# level_shifter_booster_pack.net
KiCad netlist of a schematic drawn in EAGLE
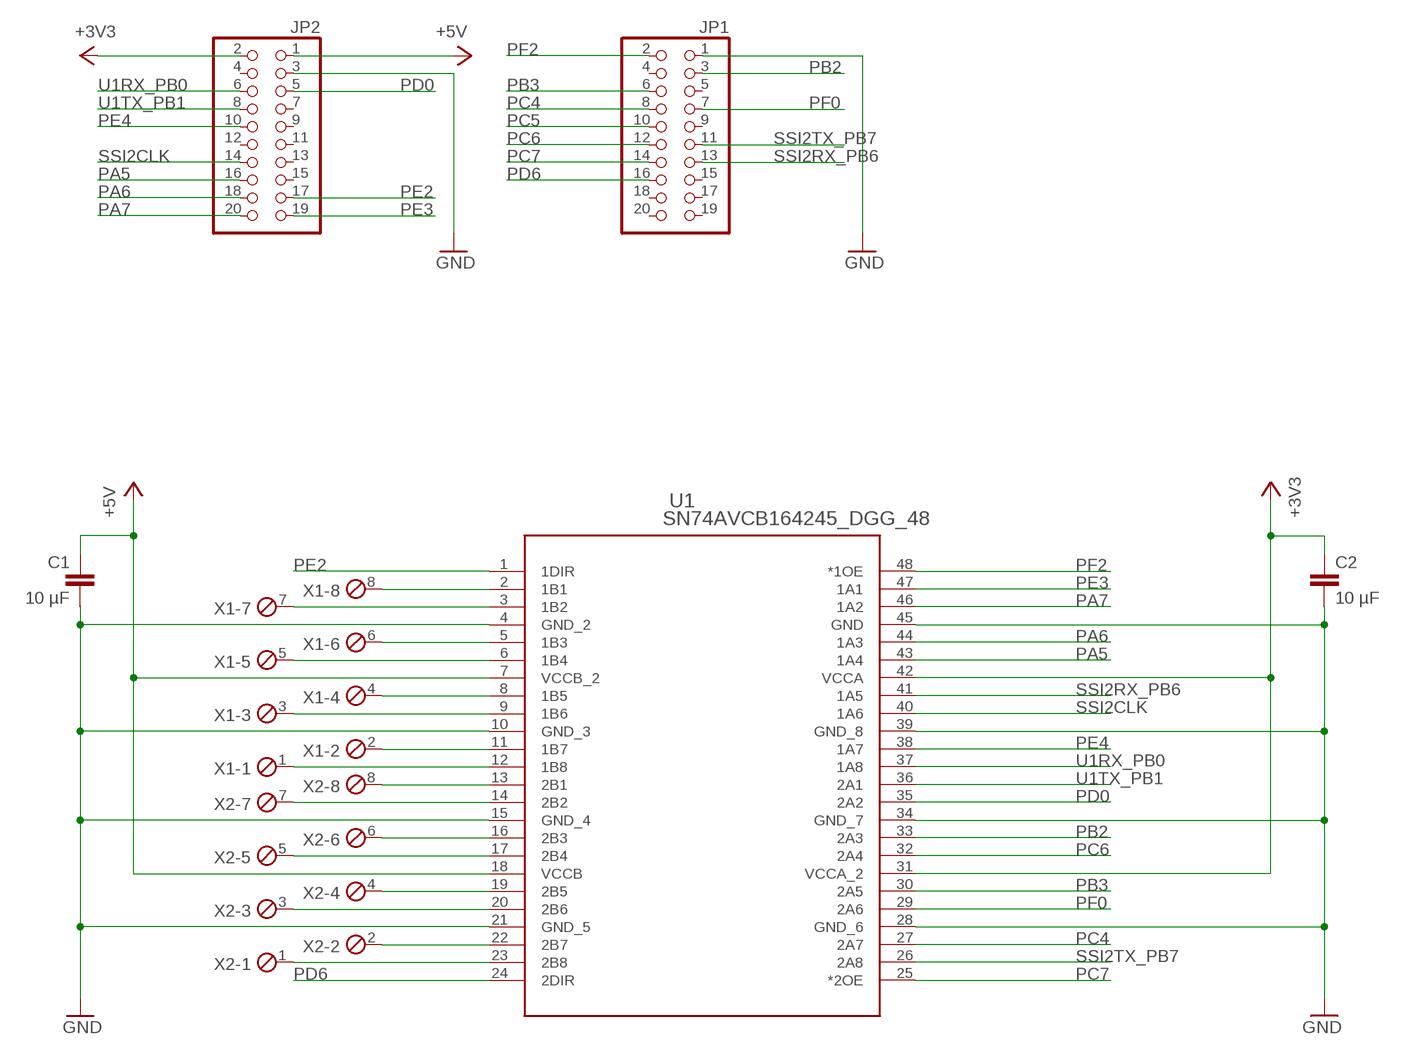
[diagram p0: schematic, sheet 1]

(export (version "E")
  (design (tool "Eeschema 10.0.6"))
  (components
    (comp (ref "C1")
      (value "10 µF")
      (footprint "eagle-import:C0805")
      (libsource (lib "eagle-import") (part "C-EUC0805"))
    )
    (comp (ref "C2")
      (value "10 µF")
      (footprint "eagle-import:C0805")
      (libsource (lib "eagle-import") (part "C-EUC0805"))
    )
    (comp (ref "JP1")
      (value "PINHD-2X10")
      (footprint "eagle-import:2X10")
      (libsource (lib "eagle-import") (part "PINHD-2X10"))
    )
    (comp (ref "JP2")
      (value "PINHD-2X10")
      (footprint "eagle-import:2X10")
      (libsource (lib "eagle-import") (part "PINHD-2X10"))
    )
    (comp (ref "U1")
      (value "SN74AVCB164245_DGG_48")
      (footprint "eagle-import:DGG48")
      (fields
        (field (name "GENERIC_PART_NUMBER") "SN74AVCB164245")
        (field (name "MANUFACTURER") "Texas Instruments")
        (field (name "MANUFACTURER_PART_NUMBER") "sn74avcb164245_dgg_48")
      )
      (libsource (lib "eagle-import") (part "SN74AVCB164245_DGG_48"))
    )
    (comp (ref "X1")
      (value "MPT8")
      (footprint "eagle-import:8POL254")
      (libsource (lib "eagle-import") (part "MPT8"))
    )
    (comp (ref "X2")
      (value "MPT8")
      (footprint "eagle-import:8POL254")
      (libsource (lib "eagle-import") (part "MPT8"))
    )
  )
  (nets
    (net (code "1") (name "+3V3") (class "Default")
      (node (ref "C2") (pin "1") (pinfunction "1_1") (pintype "passive"))
      (node (ref "JP2") (pin "2") (pinfunction "2_2") (pintype "passive"))
      (node (ref "U1") (pin "31") (pinfunction "VCCA_2_31") (pintype "power_in"))
      (node (ref "U1") (pin "42") (pinfunction "VCCA_42") (pintype "power_in"))
    )
    (net (code "2") (name "+5V") (class "Default")
      (node (ref "C1") (pin "1") (pinfunction "1_1") (pintype "passive"))
      (node (ref "JP2") (pin "1") (pinfunction "1_1") (pintype "passive"))
      (node (ref "U1") (pin "18") (pinfunction "VCCB_18") (pintype "power_in"))
      (node (ref "U1") (pin "7") (pinfunction "VCCB_2_7") (pintype "power_in"))
    )
    (net (code "3") (name "/PA5") (class "Default")
      (node (ref "JP2") (pin "16") (pinfunction "16_16") (pintype "passive"))
      (node (ref "U1") (pin "43") (pinfunction "1A4_43") (pintype "bidirectional"))
    )
    (net (code "4") (name "/PA6") (class "Default")
      (node (ref "JP2") (pin "18") (pinfunction "18_18") (pintype "passive"))
      (node (ref "U1") (pin "44") (pinfunction "1A3_44") (pintype "bidirectional"))
    )
    (net (code "5") (name "/PA7") (class "Default")
      (node (ref "JP2") (pin "20") (pinfunction "20_20") (pintype "passive"))
      (node (ref "U1") (pin "46") (pinfunction "1A2_46") (pintype "bidirectional"))
    )
    (net (code "6") (name "/PB2") (class "Default")
      (node (ref "JP1") (pin "3") (pinfunction "3_3") (pintype "passive"))
      (node (ref "U1") (pin "33") (pinfunction "2A3_33") (pintype "bidirectional"))
    )
    (net (code "7") (name "/PB3") (class "Default")
      (node (ref "JP1") (pin "6") (pinfunction "6_6") (pintype "passive"))
      (node (ref "U1") (pin "30") (pinfunction "2A5_30") (pintype "bidirectional"))
    )
    (net (code "8") (name "/PC4") (class "Default")
      (node (ref "JP1") (pin "8") (pinfunction "8_8") (pintype "passive"))
      (node (ref "U1") (pin "27") (pinfunction "2A7_27") (pintype "bidirectional"))
    )
    (net (code "9") (name "/PC5") (class "Default")
      (node (ref "JP1") (pin "10") (pinfunction "10_10") (pintype "passive"))
    )
    (net (code "10") (name "/PC6") (class "Default")
      (node (ref "JP1") (pin "12") (pinfunction "12_12") (pintype "passive"))
      (node (ref "U1") (pin "32") (pinfunction "2A4_32") (pintype "bidirectional"))
    )
    (net (code "11") (name "/PC7") (class "Default")
      (node (ref "JP1") (pin "14") (pinfunction "14_14") (pintype "passive"))
      (node (ref "U1") (pin "25") (pinfunction "*2OE_25") (pintype "input"))
    )
    (net (code "12") (name "/PD0") (class "Default")
      (node (ref "JP2") (pin "5") (pinfunction "5_5") (pintype "passive"))
      (node (ref "U1") (pin "35") (pinfunction "2A2_35") (pintype "bidirectional"))
    )
    (net (code "13") (name "/PD6") (class "Default")
      (node (ref "JP1") (pin "16") (pinfunction "16_16") (pintype "passive"))
      (node (ref "U1") (pin "24") (pinfunction "2DIR_24") (pintype "input"))
    )
    (net (code "14") (name "/PE2") (class "Default")
      (node (ref "JP2") (pin "17") (pinfunction "17_17") (pintype "passive"))
      (node (ref "U1") (pin "1") (pinfunction "1DIR_1") (pintype "input"))
    )
    (net (code "15") (name "/PE3") (class "Default")
      (node (ref "JP2") (pin "19") (pinfunction "19_19") (pintype "passive"))
      (node (ref "U1") (pin "47") (pinfunction "1A1_47") (pintype "bidirectional"))
    )
    (net (code "16") (name "/PE4") (class "Default")
      (node (ref "JP2") (pin "10") (pinfunction "10_10") (pintype "passive"))
      (node (ref "U1") (pin "38") (pinfunction "1A7_38") (pintype "bidirectional"))
    )
    (net (code "17") (name "/PF0") (class "Default")
      (node (ref "JP1") (pin "7") (pinfunction "7_7") (pintype "passive"))
      (node (ref "U1") (pin "29") (pinfunction "2A6_29") (pintype "bidirectional"))
    )
    (net (code "18") (name "/PF2") (class "Default")
      (node (ref "JP1") (pin "2") (pinfunction "2_2") (pintype "passive"))
      (node (ref "U1") (pin "48") (pinfunction "*1OE_48") (pintype "input"))
    )
    (net (code "19") (name "/SSI2CLK") (class "Default")
      (node (ref "JP2") (pin "14") (pinfunction "14_14") (pintype "passive"))
      (node (ref "U1") (pin "40") (pinfunction "1A6_40") (pintype "bidirectional"))
    )
    (net (code "20") (name "/SSI2RX_PB6") (class "Default")
      (node (ref "JP1") (pin "13") (pinfunction "13_13") (pintype "passive"))
      (node (ref "U1") (pin "41") (pinfunction "1A5_41") (pintype "bidirectional"))
    )
    (net (code "21") (name "/SSI2TX_PB7") (class "Default")
      (node (ref "JP1") (pin "11") (pinfunction "11_11") (pintype "passive"))
      (node (ref "U1") (pin "26") (pinfunction "2A8_26") (pintype "bidirectional"))
    )
    (net (code "22") (name "/U1RX_PB0") (class "Default")
      (node (ref "JP2") (pin "6") (pinfunction "6_6") (pintype "passive"))
      (node (ref "U1") (pin "37") (pinfunction "1A8_37") (pintype "bidirectional"))
    )
    (net (code "23") (name "/U1TX_PB1") (class "Default")
      (node (ref "JP2") (pin "8") (pinfunction "8_8") (pintype "passive"))
      (node (ref "U1") (pin "36") (pinfunction "2A1_36") (pintype "bidirectional"))
    )
    (net (code "24") (name "GND") (class "Default")
      (node (ref "C1") (pin "2") (pinfunction "2_2") (pintype "passive"))
      (node (ref "C2") (pin "2") (pinfunction "2_2") (pintype "passive"))
      (node (ref "JP1") (pin "1") (pinfunction "1_1") (pintype "passive"))
      (node (ref "JP2") (pin "3") (pinfunction "3_3") (pintype "passive"))
      (node (ref "U1") (pin "10") (pinfunction "GND_3_10") (pintype "power_in"))
      (node (ref "U1") (pin "15") (pinfunction "GND_4_15") (pintype "power_in"))
      (node (ref "U1") (pin "21") (pinfunction "GND_5_21") (pintype "power_in"))
      (node (ref "U1") (pin "28") (pinfunction "GND_6_28") (pintype "power_in"))
      (node (ref "U1") (pin "34") (pinfunction "GND_7_34") (pintype "power_in"))
      (node (ref "U1") (pin "39") (pinfunction "GND_8_39") (pintype "power_in"))
      (node (ref "U1") (pin "4") (pinfunction "GND_2_4") (pintype "power_in"))
      (node (ref "U1") (pin "45") (pinfunction "GND_45") (pintype "power_in"))
    )
    (net (code "25") (name "Net-(U1-1B1)") (class "Default")
      (node (ref "U1") (pin "2") (pinfunction "1B1_2") (pintype "bidirectional"))
      (node (ref "X1") (pin "8") (pinfunction "1_8") (pintype "passive"))
    )
    (net (code "26") (name "Net-(U1-1B2)") (class "Default")
      (node (ref "U1") (pin "3") (pinfunction "1B2_3") (pintype "bidirectional"))
      (node (ref "X1") (pin "7") (pinfunction "1_7") (pintype "passive"))
    )
    (net (code "27") (name "Net-(U1-1B3)") (class "Default")
      (node (ref "U1") (pin "5") (pinfunction "1B3_5") (pintype "bidirectional"))
      (node (ref "X1") (pin "6") (pinfunction "1_6") (pintype "passive"))
    )
    (net (code "28") (name "Net-(U1-1B4)") (class "Default")
      (node (ref "U1") (pin "6") (pinfunction "1B4_6") (pintype "bidirectional"))
      (node (ref "X1") (pin "5") (pinfunction "1_5") (pintype "passive"))
    )
    (net (code "29") (name "Net-(U1-1B5)") (class "Default")
      (node (ref "U1") (pin "8") (pinfunction "1B5_8") (pintype "bidirectional"))
      (node (ref "X1") (pin "4") (pinfunction "1_4") (pintype "passive"))
    )
    (net (code "30") (name "Net-(U1-1B6)") (class "Default")
      (node (ref "U1") (pin "9") (pinfunction "1B6_9") (pintype "bidirectional"))
      (node (ref "X1") (pin "3") (pinfunction "1_3") (pintype "passive"))
    )
    (net (code "31") (name "Net-(U1-1B7)") (class "Default")
      (node (ref "U1") (pin "11") (pinfunction "1B7_11") (pintype "bidirectional"))
      (node (ref "X1") (pin "2") (pinfunction "1_2") (pintype "passive"))
    )
    (net (code "32") (name "Net-(U1-1B8)") (class "Default")
      (node (ref "U1") (pin "12") (pinfunction "1B8_12") (pintype "bidirectional"))
      (node (ref "X1") (pin "1") (pinfunction "1_1") (pintype "passive"))
    )
    (net (code "33") (name "Net-(U1-2B1)") (class "Default")
      (node (ref "U1") (pin "13") (pinfunction "2B1_13") (pintype "bidirectional"))
      (node (ref "X2") (pin "8") (pinfunction "1_8") (pintype "passive"))
    )
    (net (code "34") (name "Net-(U1-2B2)") (class "Default")
      (node (ref "U1") (pin "14") (pinfunction "2B2_14") (pintype "bidirectional"))
      (node (ref "X2") (pin "7") (pinfunction "1_7") (pintype "passive"))
    )
    (net (code "35") (name "Net-(U1-2B3)") (class "Default")
      (node (ref "U1") (pin "16") (pinfunction "2B3_16") (pintype "bidirectional"))
      (node (ref "X2") (pin "6") (pinfunction "1_6") (pintype "passive"))
    )
    (net (code "36") (name "Net-(U1-2B4)") (class "Default")
      (node (ref "U1") (pin "17") (pinfunction "2B4_17") (pintype "bidirectional"))
      (node (ref "X2") (pin "5") (pinfunction "1_5") (pintype "passive"))
    )
    (net (code "37") (name "Net-(U1-2B5)") (class "Default")
      (node (ref "U1") (pin "19") (pinfunction "2B5_19") (pintype "bidirectional"))
      (node (ref "X2") (pin "4") (pinfunction "1_4") (pintype "passive"))
    )
    (net (code "38") (name "Net-(U1-2B6)") (class "Default")
      (node (ref "U1") (pin "20") (pinfunction "2B6_20") (pintype "bidirectional"))
      (node (ref "X2") (pin "3") (pinfunction "1_3") (pintype "passive"))
    )
    (net (code "39") (name "Net-(U1-2B7)") (class "Default")
      (node (ref "U1") (pin "22") (pinfunction "2B7_22") (pintype "bidirectional"))
      (node (ref "X2") (pin "2") (pinfunction "1_2") (pintype "passive"))
    )
    (net (code "40") (name "Net-(U1-2B8)") (class "Default")
      (node (ref "U1") (pin "23") (pinfunction "2B8_23") (pintype "bidirectional"))
      (node (ref "X2") (pin "1") (pinfunction "1_1") (pintype "passive"))
    )
    (net (code "41") (name "unconnected-(JP1-Pad4)") (class "Default")
      (node (ref "JP1") (pin "4") (pinfunction "4_4") (pintype "passive"))
    )
    (net (code "42") (name "unconnected-(JP1-Pad5)") (class "Default")
      (node (ref "JP1") (pin "5") (pinfunction "5_5") (pintype "passive"))
    )
    (net (code "43") (name "unconnected-(JP1-Pad9)") (class "Default")
      (node (ref "JP1") (pin "9") (pinfunction "9_9") (pintype "passive"))
    )
    (net (code "44") (name "unconnected-(JP1-Pad15)") (class "Default")
      (node (ref "JP1") (pin "15") (pinfunction "15_15") (pintype "passive"))
    )
    (net (code "45") (name "unconnected-(JP1-Pad17)") (class "Default")
      (node (ref "JP1") (pin "17") (pinfunction "17_17") (pintype "passive"))
    )
    (net (code "46") (name "unconnected-(JP1-Pad18)") (class "Default")
      (node (ref "JP1") (pin "18") (pinfunction "18_18") (pintype "passive"))
    )
    (net (code "47") (name "unconnected-(JP1-Pad19)") (class "Default")
      (node (ref "JP1") (pin "19") (pinfunction "19_19") (pintype "passive"))
    )
    (net (code "48") (name "unconnected-(JP1-Pad20)") (class "Default")
      (node (ref "JP1") (pin "20") (pinfunction "20_20") (pintype "passive"))
    )
    (net (code "49") (name "unconnected-(JP2-Pad4)") (class "Default")
      (node (ref "JP2") (pin "4") (pinfunction "4_4") (pintype "passive"))
    )
    (net (code "50") (name "unconnected-(JP2-Pad7)") (class "Default")
      (node (ref "JP2") (pin "7") (pinfunction "7_7") (pintype "passive"))
    )
    (net (code "51") (name "unconnected-(JP2-Pad9)") (class "Default")
      (node (ref "JP2") (pin "9") (pinfunction "9_9") (pintype "passive"))
    )
    (net (code "52") (name "unconnected-(JP2-Pad11)") (class "Default")
      (node (ref "JP2") (pin "11") (pinfunction "11_11") (pintype "passive"))
    )
    (net (code "53") (name "unconnected-(JP2-Pad12)") (class "Default")
      (node (ref "JP2") (pin "12") (pinfunction "12_12") (pintype "passive"))
    )
    (net (code "54") (name "unconnected-(JP2-Pad13)") (class "Default")
      (node (ref "JP2") (pin "13") (pinfunction "13_13") (pintype "passive"))
    )
    (net (code "55") (name "unconnected-(JP2-Pad15)") (class "Default")
      (node (ref "JP2") (pin "15") (pinfunction "15_15") (pintype "passive"))
    )
  )
)
